# pcb_3_0.net
KiCad netlist of a schematic drawn in EAGLE
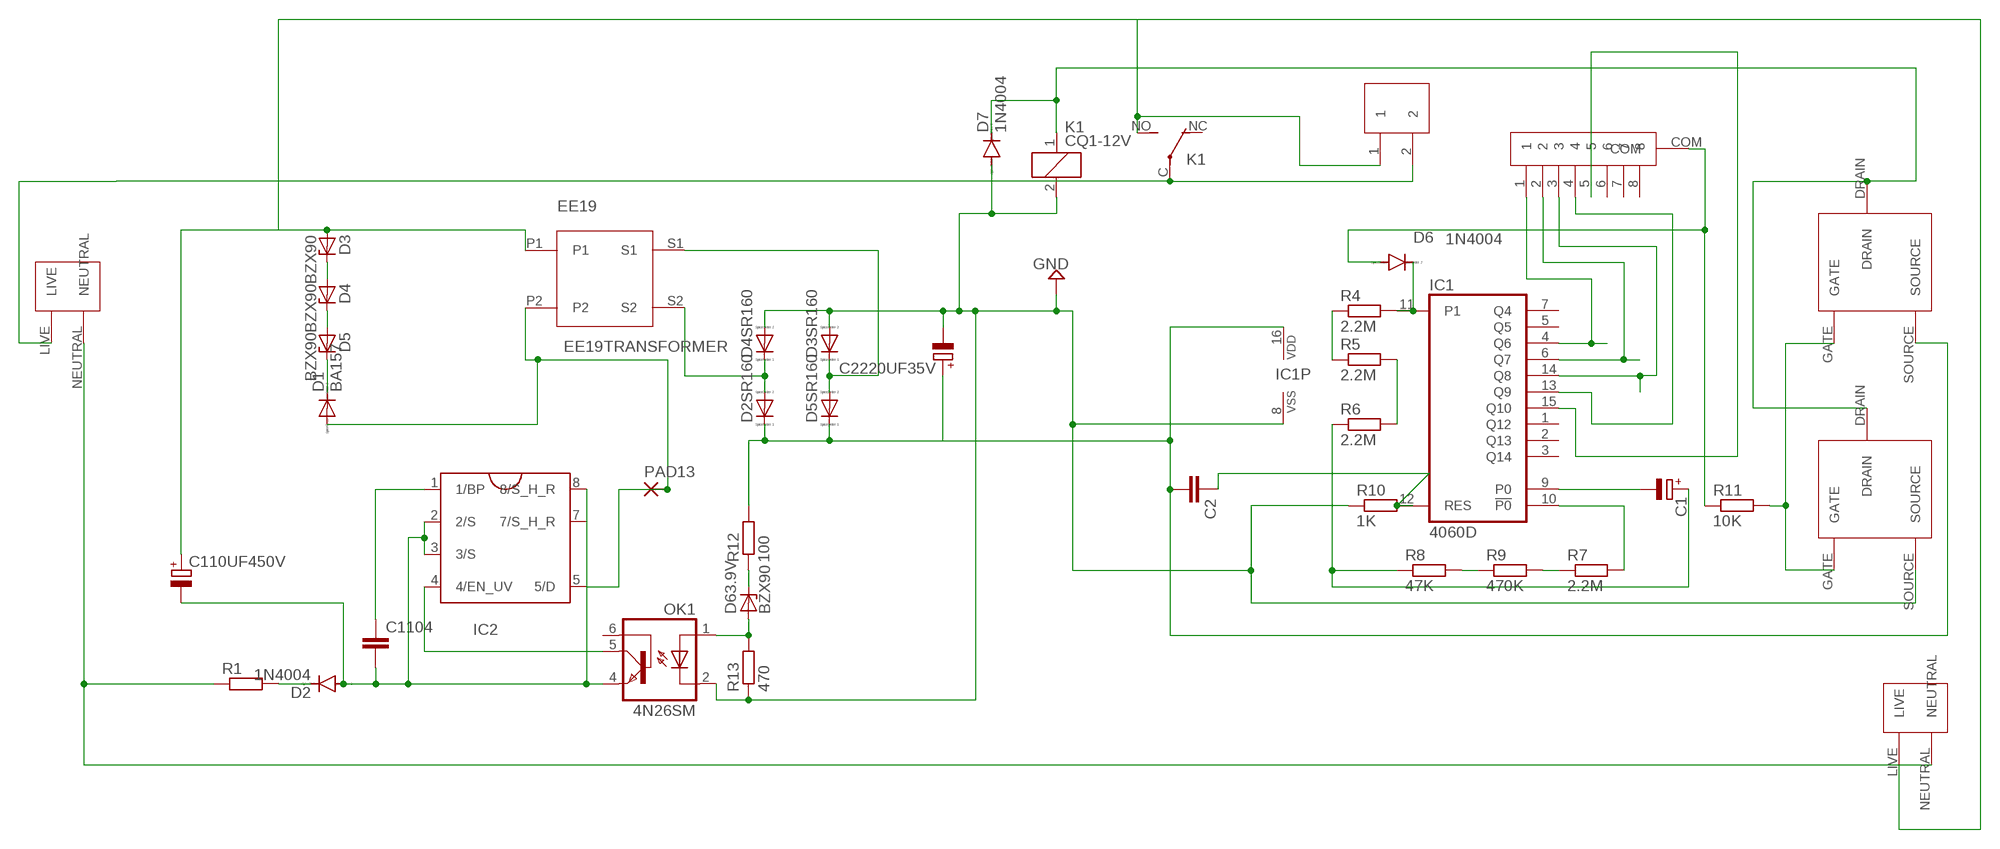
[diagram p0: schematic, sheet 1]

(export (version "E")
  (design (tool "Eeschema 10.0.6"))
  (components
    (comp (ref "C1")
      (value "CPOL-EUE2.5-6")
      (footprint "eagle-import:E2,5-6")
      (libsource (lib "eagle-import") (part "CPOL-EUE2.5-6"))
    )
    (comp (ref "C2")
      (value "C-EU025-025X050")
      (footprint "eagle-import:C025-025X050")
      (libsource (lib "eagle-import") (part "C-EU025-025X050"))
    )
    (comp (ref "C110UF450V")
      (value "CPOL-EUE5-10.5")
      (footprint "eagle-import:E5-10,5")
      (libsource (lib "eagle-import") (part "CPOL-EUE5-10.5"))
    )
    (comp (ref "C1104")
      (value "C-EU025-024X044")
      (footprint "eagle-import:C025-024X044")
      (libsource (lib "eagle-import") (part "C-EU025-024X044"))
    )
    (comp (ref "C2220UF35V")
      (value "CPOL-EUE3.5-8")
      (footprint "eagle-import:E3,5-8")
      (libsource (lib "eagle-import") (part "CPOL-EUE3.5-8"))
    )
    (comp (ref "D1")
      (value "BA157")
      (footprint "eagle-import:P1-10")
      (libsource (lib "eagle-import") (part "BA157"))
    )
    (comp (ref "D2")
      (value "1N4004")
      (footprint "eagle-import:DO41-10")
      (libsource (lib "eagle-import") (part "1N4004"))
    )
    (comp (ref "D2SR160")
      (value "DIODE_E-DO35-7")
      (footprint "eagle-import:DIODE_DO35-7")
      (libsource (lib "eagle-import") (part "DIODE_E-DO35-7"))
    )
    (comp (ref "D3")
      (value "BZX90")
      (footprint "eagle-import:DO34Z7")
      (libsource (lib "eagle-import") (part "BZX90"))
    )
    (comp (ref "D3SR160")
      (value "DIODE_E-DO35-7")
      (footprint "eagle-import:DIODE_DO35-7")
      (libsource (lib "eagle-import") (part "DIODE_E-DO35-7"))
    )
    (comp (ref "D4")
      (value "BZX90")
      (footprint "eagle-import:DO34Z7")
      (libsource (lib "eagle-import") (part "BZX90"))
    )
    (comp (ref "D4SR160")
      (value "DIODE_E-DO35-7")
      (footprint "eagle-import:DIODE_DO35-7")
      (libsource (lib "eagle-import") (part "DIODE_E-DO35-7"))
    )
    (comp (ref "D5")
      (value "BZX90")
      (footprint "eagle-import:DO34Z7")
      (libsource (lib "eagle-import") (part "BZX90"))
    )
    (comp (ref "D5SR160")
      (value "DIODE_E-DO35-7")
      (footprint "eagle-import:DIODE_DO35-7")
      (libsource (lib "eagle-import") (part "DIODE_E-DO35-7"))
    )
    (comp (ref "D6")
      (value "1N4004")
      (footprint "eagle-import:DO41-10")
      (libsource (lib "eagle-import") (part "1N4004"))
    )
    (comp (ref "D7")
      (value "1N4004")
      (footprint "eagle-import:DO41-10")
      (libsource (lib "eagle-import") (part "1N4004"))
    )
    (comp (ref "D63.9V")
      (value "BZX90")
      (footprint "eagle-import:DO34Z7")
      (libsource (lib "eagle-import") (part "BZX90"))
    )
    (comp (ref "IC1")
      (value "4060D")
      (footprint "eagle-import:SO16")
      (fields (field (name "SPICEPREFIX") "X"))
      (libsource (lib "eagle-import") (part "4060D"))
    )
    (comp (ref "IC2")
      (value "TNY263-268")
      (footprint "eagle-import:DIP8B_SMD(G_PACKAGE)")
      (fields (field (name "SPICEPREFIX") "X"))
      (libsource (lib "eagle-import") (part "TNY263-268"))
    )
    (comp (ref "K1")
      (value "CQ1-12V")
      (footprint "eagle-import:CQ1")
      (libsource (lib "eagle-import") (part "CQ1-12V"))
    )
    (comp (ref "OK1")
      (value "4N26SM")
      (footprint "eagle-import:DIL6-SMD")
      (libsource (lib "eagle-import") (part "4N?MS26"))
    )
    (comp (ref "PAD13")
      (value "2,15/1,0")
      (footprint "eagle-import:2,15_1,0")
      (libsource (lib "eagle-import") (part "2,15/1,0"))
    )
    (comp (ref "R1")
      (value "R-EU_0207/10")
      (footprint "eagle-import:0207_10")
      (libsource (lib "eagle-import") (part "R-EU_0207/10"))
    )
    (comp (ref "R4")
      (value "2.2M")
      (footprint "eagle-import:0204_5")
      (libsource (lib "eagle-import") (part "resistor_348_R-EU_0204/5"))
    )
    (comp (ref "R5")
      (value "2.2M")
      (footprint "eagle-import:0204_5")
      (libsource (lib "eagle-import") (part "resistor_348_R-EU_0204/5"))
    )
    (comp (ref "R6")
      (value "2.2M")
      (footprint "eagle-import:0204_5")
      (libsource (lib "eagle-import") (part "resistor_348_R-EU_0204/5"))
    )
    (comp (ref "R7")
      (value "2.2M")
      (footprint "eagle-import:0204_5")
      (libsource (lib "eagle-import") (part "resistor_348_R-EU_0204/5"))
    )
    (comp (ref "R8")
      (value "47K")
      (footprint "eagle-import:0204_5")
      (libsource (lib "eagle-import") (part "resistor_348_R-EU_0204/5"))
    )
    (comp (ref "R9")
      (value "470K")
      (footprint "eagle-import:0204_5")
      (libsource (lib "eagle-import") (part "resistor_348_R-EU_0204/5"))
    )
    (comp (ref "R10")
      (value "1K")
      (footprint "eagle-import:0204_5")
      (libsource (lib "eagle-import") (part "resistor_348_R-EU_0204/5"))
    )
    (comp (ref "R11")
      (value "10K")
      (footprint "eagle-import:0204_5")
      (libsource (lib "eagle-import") (part "resistor_348_R-EU_0204/5"))
    )
    (comp (ref "R12")
      (value "100")
      (footprint "eagle-import:0204_5")
      (libsource (lib "eagle-import") (part "resistor_348_R-EU_0204/5"))
    )
    (comp (ref "R13")
      (value "470")
      (footprint "eagle-import:0204_5")
      (libsource (lib "eagle-import") (part "resistor_348_R-EU_0204/5"))
    )
    (comp (ref "U$1")
      (value "EE19TRANSFORMER")
      (footprint "eagle-import:EE19")
      (libsource (lib "eagle-import") (part "EE19TRANSFORMER"))
    )
    (comp (ref "U$2")
      (value "FR9024N")
      (footprint "eagle-import:FR9024N")
      (libsource (lib "eagle-import") (part "FR9024N"))
    )
    (comp (ref "U$3")
      (value "FR9024N")
      (footprint "eagle-import:FR9024N")
      (libsource (lib "eagle-import") (part "FR9024N"))
    )
    (comp (ref "U$4")
      (value "AC_INPUT")
      (footprint "eagle-import:AC_INPUT")
      (libsource (lib "eagle-import") (part "AC_INPUT"))
    )
    (comp (ref "U$5")
      (value "AC_INPUT")
      (footprint "eagle-import:AC_INPUT")
      (libsource (lib "eagle-import") (part "AC_INPUT"))
    )
    (comp (ref "U$6")
      (value "AC_PUSH_BUTTON")
      (footprint "eagle-import:AC_PUSH_BUTTON")
      (libsource (lib "eagle-import") (part "AC_PUSH_BUTTON"))
    )
    (comp (ref "U$7")
      (value "SINGLE_POLE_5_TRS")
      (footprint "eagle-import:SINGLE_POLE_8_TRS")
      (libsource (lib "eagle-import") (part "SINGLE_POLE_5_TRS"))
    )
  )
  (nets
    (net (code "1") (name "GND") (class "Default")
      (node (ref "C2220UF35V") (pin "-") (pinfunction "-_-") (pintype "passive"))
      (node (ref "D3SR160") (pin "A") (pinfunction "C_A") (pintype "passive"))
      (node (ref "D4SR160") (pin "A") (pinfunction "C_A") (pintype "passive"))
      (node (ref "D7") (pin "A") (pinfunction "A_A") (pintype "passive"))
      (node (ref "IC1") (pin "8") (pinfunction "VSS_8") (pintype "power_in"))
      (node (ref "K1") (pin "2") (pinfunction "2_2") (pintype "passive"))
      (node (ref "OK1") (pin "2") (pinfunction "C_2") (pintype "passive"))
      (node (ref "R10") (pin "1") (pinfunction "1_1") (pintype "passive"))
      (node (ref "R13") (pin "1") (pinfunction "1_1") (pintype "passive"))
      (node (ref "U$2") (pin "SOURCE") (pinfunction "SOURCE_SOURCE") (pintype "bidirectional"))
    )
    (net (code "2") (name "Net-(C1-Pad+)") (class "Default")
      (node (ref "C1") (pin "+") (pinfunction "+_+") (pintype "passive"))
      (node (ref "R6") (pin "1") (pinfunction "1_1") (pintype "passive"))
      (node (ref "R8") (pin "1") (pinfunction "1_1") (pintype "passive"))
    )
    (net (code "3") (name "Net-(D1-PadC)") (class "Default")
      (node (ref "D1") (pin "C") (pinfunction "C_C") (pintype "passive"))
      (node (ref "D5") (pin "C") (pinfunction "C_C") (pintype "passive"))
    )
    (net (code "4") (name "Net-(D2-PadC)") (class "Default")
      (node (ref "D2") (pin "C") (pinfunction "C_C") (pintype "passive"))
      (node (ref "R1") (pin "2") (pinfunction "2_2") (pintype "passive"))
    )
    (net (code "5") (name "Net-(D2SR160-A)") (class "Default")
      (node (ref "C2") (pin "2") (pinfunction "2_2") (pintype "passive"))
      (node (ref "C2220UF35V") (pin "+") (pinfunction "+_+") (pintype "passive"))
      (node (ref "D2SR160") (pin "C") (pinfunction "A_C") (pintype "passive"))
      (node (ref "D5SR160") (pin "C") (pinfunction "A_C") (pintype "passive"))
      (node (ref "IC1") (pin "16") (pinfunction "VDD_16") (pintype "power_in"))
      (node (ref "R12") (pin "2") (pinfunction "2_2") (pintype "passive"))
      (node (ref "U$3") (pin "SOURCE") (pinfunction "SOURCE_SOURCE") (pintype "bidirectional"))
    )
    (net (code "6") (name "Net-(D2SR160-C)") (class "Default")
      (node (ref "D2SR160") (pin "A") (pinfunction "C_A") (pintype "passive"))
      (node (ref "D4SR160") (pin "C") (pinfunction "A_C") (pintype "passive"))
      (node (ref "U$1") (pin "S2") (pinfunction "S2_S2") (pintype "bidirectional"))
    )
    (net (code "7") (name "Net-(D3-PadC)") (class "Default")
      (node (ref "D3") (pin "C") (pinfunction "C_C") (pintype "passive"))
      (node (ref "D4") (pin "A") (pinfunction "A_A") (pintype "passive"))
    )
    (net (code "8") (name "Net-(D3SR160-A)") (class "Default")
      (node (ref "D3SR160") (pin "C") (pinfunction "A_C") (pintype "passive"))
      (node (ref "D5SR160") (pin "A") (pinfunction "C_A") (pintype "passive"))
      (node (ref "U$1") (pin "S1") (pinfunction "S1_S1") (pintype "bidirectional"))
    )
    (net (code "9") (name "Net-(D4-PadC)") (class "Default")
      (node (ref "D4") (pin "C") (pinfunction "C_C") (pintype "passive"))
      (node (ref "D5") (pin "A") (pinfunction "A_A") (pintype "passive"))
    )
    (net (code "10") (name "Net-(D6-PadA)") (class "Default")
      (node (ref "D6") (pin "A") (pinfunction "A_A") (pintype "passive"))
      (node (ref "R11") (pin "1") (pinfunction "1_1") (pintype "passive"))
      (node (ref "U$7") (pin "COM") (pinfunction "COM_COM") (pintype "bidirectional"))
    )
    (net (code "11") (name "Net-(D7-PadC)") (class "Default")
      (node (ref "D7") (pin "C") (pinfunction "C_C") (pintype "passive"))
      (node (ref "K1") (pin "1") (pinfunction "1_1") (pintype "passive"))
      (node (ref "U$2") (pin "DRAIN") (pinfunction "DRAIN_DRAIN") (pintype "bidirectional"))
      (node (ref "U$3") (pin "DRAIN") (pinfunction "DRAIN_DRAIN") (pintype "bidirectional"))
    )
    (net (code "12") (name "Net-(D63.9V-PadC)") (class "Default")
      (node (ref "D63.9V") (pin "C") (pinfunction "C_C") (pintype "passive"))
      (node (ref "R12") (pin "1") (pinfunction "1_1") (pintype "passive"))
    )
    (net (code "13") (name "Net-(IC1A-P0)") (class "Default")
      (node (ref "C1") (pin "-") (pinfunction "-_-") (pintype "passive"))
      (node (ref "IC1") (pin "9") (pinfunction "P0_9") (pintype "output"))
    )
    (net (code "14") (name "Net-(IC1A-P1)") (class "Default")
      (node (ref "D6") (pin "C") (pinfunction "C_C") (pintype "passive"))
      (node (ref "IC1") (pin "11") (pinfunction "P1_11") (pintype "input"))
      (node (ref "R4") (pin "2") (pinfunction "2_2") (pintype "passive"))
    )
    (net (code "15") (name "Net-(IC1A-Q6)") (class "Default")
      (node (ref "IC1") (pin "4") (pinfunction "Q6_4") (pintype "output"))
      (node (ref "U$7") (pin "1") (pinfunction "1_1") (pintype "bidirectional"))
    )
    (net (code "16") (name "Net-(IC1A-Q7)") (class "Default")
      (node (ref "IC1") (pin "6") (pinfunction "Q7_6") (pintype "output"))
      (node (ref "U$7") (pin "2") (pinfunction "2_2") (pintype "bidirectional"))
    )
    (net (code "17") (name "Net-(IC1A-Q8)") (class "Default")
      (node (ref "IC1") (pin "14") (pinfunction "Q8_14") (pintype "output"))
      (node (ref "U$7") (pin "3") (pinfunction "3_3") (pintype "bidirectional"))
    )
    (net (code "18") (name "Net-(IC1A-Q9)") (class "Default")
      (node (ref "IC1") (pin "13") (pinfunction "Q9_13") (pintype "output"))
      (node (ref "U$7") (pin "4") (pinfunction "4_4") (pintype "bidirectional"))
    )
    (net (code "19") (name "Net-(IC1A-Q10)") (class "Default")
      (node (ref "IC1") (pin "15") (pinfunction "Q10_15") (pintype "output"))
      (node (ref "U$7") (pin "5") (pinfunction "5_5") (pintype "bidirectional"))
    )
    (net (code "20") (name "Net-(IC1A-RES)") (class "Default")
      (node (ref "C2") (pin "1") (pinfunction "1_1") (pintype "passive"))
      (node (ref "IC1") (pin "12") (pinfunction "RES_12") (pintype "input"))
      (node (ref "R10") (pin "2") (pinfunction "2_2") (pintype "passive"))
    )
    (net (code "21") (name "Net-(IC1A-~{P0})") (class "Default")
      (node (ref "IC1") (pin "10") (pinfunction "~{P0}_10") (pintype "output"))
      (node (ref "R7") (pin "2") (pinfunction "2_2") (pintype "passive"))
    )
    (net (code "22") (name "Net-(IC2-1{slash}BP)") (class "Default")
      (node (ref "C1104") (pin "1") (pinfunction "1_1") (pintype "passive"))
      (node (ref "IC2") (pin "1") (pinfunction "1/BP_1") (pintype "bidirectional"))
    )
    (net (code "23") (name "Net-(IC2-2{slash}S)") (class "Default")
      (node (ref "C1104") (pin "2") (pinfunction "2_2") (pintype "passive"))
      (node (ref "C110UF450V") (pin "-") (pinfunction "-_-") (pintype "passive"))
      (node (ref "D2") (pin "A") (pinfunction "A_A") (pintype "passive"))
      (node (ref "IC2") (pin "2") (pinfunction "2/S_2") (pintype "bidirectional"))
      (node (ref "IC2") (pin "3") (pinfunction "3/S_3") (pintype "bidirectional"))
      (node (ref "IC2") (pin "7") (pinfunction "7/S_H_R_7") (pintype "bidirectional"))
      (node (ref "IC2") (pin "8") (pinfunction "8/S_H_R_8") (pintype "bidirectional"))
      (node (ref "OK1") (pin "4") (pinfunction "EMI_4") (pintype "passive"))
    )
    (net (code "24") (name "Net-(IC2-4{slash}EN_UV)") (class "Default")
      (node (ref "IC2") (pin "4") (pinfunction "4/EN_UV_4") (pintype "bidirectional"))
      (node (ref "OK1") (pin "5") (pinfunction "COL_5") (pintype "passive"))
    )
    (net (code "25") (name "Net-(IC2-5{slash}D)") (class "Default")
      (node (ref "D1") (pin "A") (pinfunction "A_A") (pintype "passive"))
      (node (ref "IC2") (pin "5") (pinfunction "5/D_5") (pintype "bidirectional"))
      (node (ref "PAD13") (pin "1") (pinfunction "P_1") (pintype "passive"))
      (node (ref "U$1") (pin "P2") (pinfunction "P2_P2") (pintype "bidirectional"))
    )
    (net (code "26") (name "Net-(K1B-P)") (class "Default")
      (node (ref "K1") (pin "C") (pinfunction "P_C") (pintype "passive"))
      (node (ref "U$4") (pin "LIVE") (pinfunction "LIVE_LIVE") (pintype "bidirectional"))
      (node (ref "U$6") (pin "2") (pinfunction "2_2") (pintype "bidirectional"))
    )
    (net (code "27") (name "Net-(K1B-S)") (class "Default")
      (node (ref "C110UF450V") (pin "+") (pinfunction "+_+") (pintype "passive"))
      (node (ref "D3") (pin "A") (pinfunction "A_A") (pintype "passive"))
      (node (ref "K1") (pin "NO") (pinfunction "S_NO") (pintype "passive"))
      (node (ref "U$1") (pin "P1") (pinfunction "P1_P1") (pintype "bidirectional"))
      (node (ref "U$5") (pin "LIVE") (pinfunction "LIVE_LIVE") (pintype "bidirectional"))
      (node (ref "U$6") (pin "1") (pinfunction "1_1") (pintype "bidirectional"))
    )
    (net (code "28") (name "Net-(OK1-A)") (class "Default")
      (node (ref "D63.9V") (pin "A") (pinfunction "A_A") (pintype "passive"))
      (node (ref "OK1") (pin "1") (pinfunction "A_1") (pintype "passive"))
      (node (ref "R13") (pin "2") (pinfunction "2_2") (pintype "passive"))
    )
    (net (code "29") (name "Net-(R1-Pad1)") (class "Default")
      (node (ref "R1") (pin "1") (pinfunction "1_1") (pintype "passive"))
      (node (ref "U$4") (pin "NEUTRAL") (pinfunction "NEUTRAL_NEUTRAL") (pintype "bidirectional"))
      (node (ref "U$5") (pin "NEUTRAL") (pinfunction "NEUTRAL_NEUTRAL") (pintype "bidirectional"))
    )
    (net (code "30") (name "Net-(R4-Pad1)") (class "Default")
      (node (ref "R4") (pin "1") (pinfunction "1_1") (pintype "passive"))
      (node (ref "R5") (pin "1") (pinfunction "1_1") (pintype "passive"))
    )
    (net (code "31") (name "Net-(R5-Pad2)") (class "Default")
      (node (ref "R5") (pin "2") (pinfunction "2_2") (pintype "passive"))
      (node (ref "R6") (pin "2") (pinfunction "2_2") (pintype "passive"))
    )
    (net (code "32") (name "Net-(R7-Pad1)") (class "Default")
      (node (ref "R7") (pin "1") (pinfunction "1_1") (pintype "passive"))
      (node (ref "R9") (pin "2") (pinfunction "2_2") (pintype "passive"))
    )
    (net (code "33") (name "Net-(R8-Pad2)") (class "Default")
      (node (ref "R8") (pin "2") (pinfunction "2_2") (pintype "passive"))
      (node (ref "R9") (pin "1") (pinfunction "1_1") (pintype "passive"))
    )
    (net (code "34") (name "Net-(R11-Pad2)") (class "Default")
      (node (ref "R11") (pin "2") (pinfunction "2_2") (pintype "passive"))
      (node (ref "U$2") (pin "GATE") (pinfunction "GATE_GATE") (pintype "bidirectional"))
      (node (ref "U$3") (pin "GATE") (pinfunction "GATE_GATE") (pintype "bidirectional"))
    )
    (net (code "35") (name "unconnected-(IC1A-Q4-Pad7)") (class "Default")
      (node (ref "IC1") (pin "7") (pinfunction "Q4_7") (pintype "output"))
    )
    (net (code "36") (name "unconnected-(IC1A-Q5-Pad5)") (class "Default")
      (node (ref "IC1") (pin "5") (pinfunction "Q5_5") (pintype "output"))
    )
    (net (code "37") (name "unconnected-(IC1A-Q12-Pad1)") (class "Default")
      (node (ref "IC1") (pin "1") (pinfunction "Q12_1") (pintype "output"))
    )
    (net (code "38") (name "unconnected-(IC1A-Q13-Pad2)") (class "Default")
      (node (ref "IC1") (pin "2") (pinfunction "Q13_2") (pintype "output"))
    )
    (net (code "39") (name "unconnected-(IC1A-Q14-Pad3)") (class "Default")
      (node (ref "IC1") (pin "3") (pinfunction "Q14_3") (pintype "output"))
    )
    (net (code "40") (name "unconnected-(K1B-O-PadNC)") (class "Default")
      (node (ref "K1") (pin "NC") (pinfunction "O_NC") (pintype "passive"))
    )
    (net (code "41") (name "unconnected-(OK1-BAS-Pad6)") (class "Default")
      (node (ref "OK1") (pin "6") (pinfunction "BAS_6") (pintype "passive"))
    )
    (net (code "42") (name "unconnected-(U$7-Pad6)") (class "Default")
      (node (ref "U$7") (pin "6") (pinfunction "6_6") (pintype "bidirectional"))
    )
    (net (code "43") (name "unconnected-(U$7-Pad7)") (class "Default")
      (node (ref "U$7") (pin "7") (pinfunction "7_7") (pintype "bidirectional"))
    )
    (net (code "44") (name "unconnected-(U$7-Pad8)") (class "Default")
      (node (ref "U$7") (pin "8") (pinfunction "8_8") (pintype "bidirectional"))
    )
  )
)
